# v1.net
KiCad netlist of a schematic drawn in EAGLE
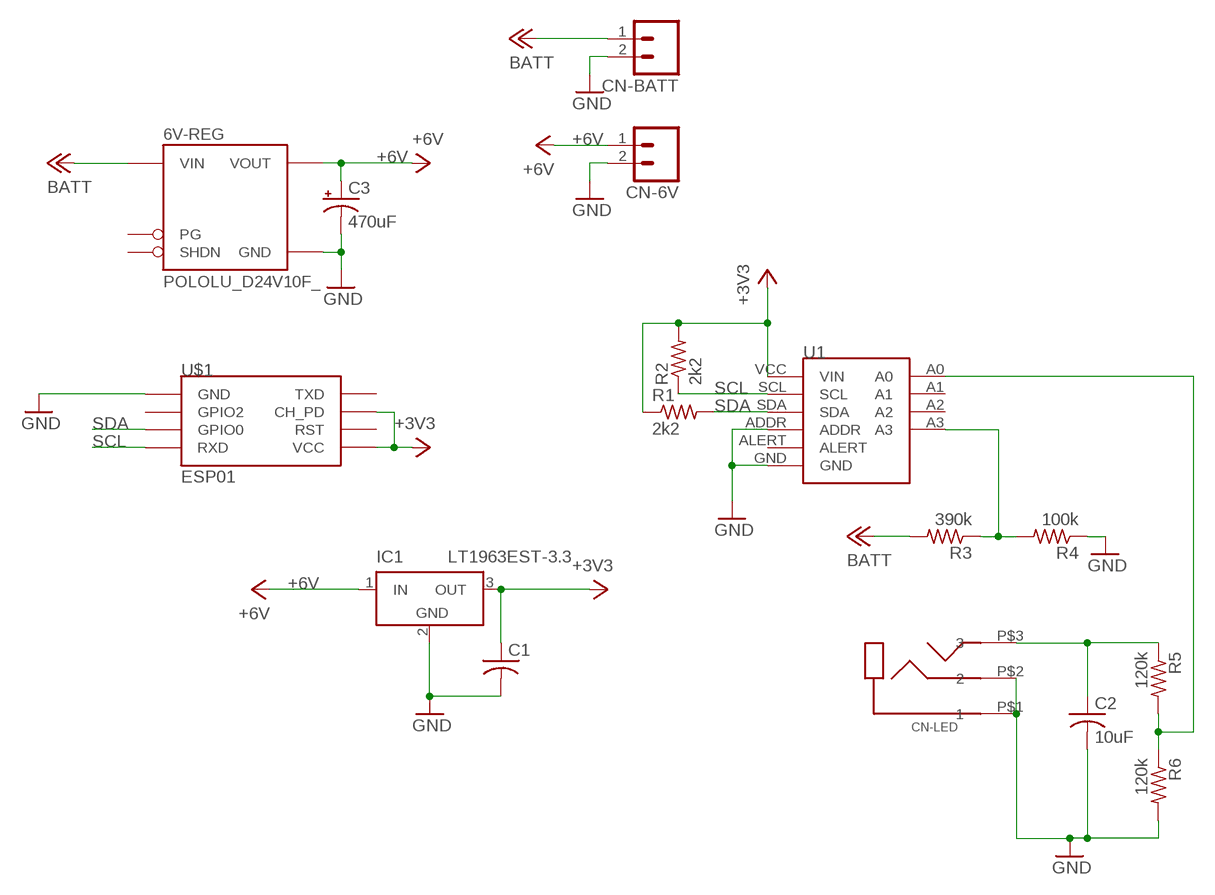
[diagram p0: schematic, sheet 1]

(export (version "E")
  (design (tool "Eeschema 10.0.6"))
  (components
    (comp (ref "6V-REG")
      (value "POLOLU_D24V10F_")
      (footprint "eagle-import:POLOLU_D24V10")
      (libsource (lib "eagle-import") (part "POLOLU_D24V10F_"))
    )
    (comp (ref "C1")
      (value "C-USC1210")
      (footprint "eagle-import:C1210")
      (libsource (lib "eagle-import") (part "C-USC1210"))
    )
    (comp (ref "C2")
      (value "10uF")
      (footprint "eagle-import:C0805K")
      (libsource (lib "eagle-import") (part "C-USC0805K"))
    )
    (comp (ref "C3")
      (value "470uF")
      (footprint "eagle-import:CPOL-RADIAL-2.5MM-6.5MM")
      (libsource (lib "eagle-import") (part "100UF-POLAR-RADIAL-2.5MM-25V-20%"))
    )
    (comp (ref "CN-6V")
      (value "M02")
      (footprint "eagle-import:02P")
      (libsource (lib "eagle-import") (part "M02"))
    )
    (comp (ref "CN-BATT")
      (value "M02")
      (footprint "eagle-import:02P")
      (libsource (lib "eagle-import") (part "M02"))
    )
    (comp (ref "CN-LED")
      (value "PJ-320B")
      (footprint "eagle-import:PJ-320B")
      (libsource (lib "eagle-import") (part "PJ-320B"))
    )
    (comp (ref "IC1")
      (value "LT1963EST-3.3")
      (footprint "eagle-import:SOT223")
      (libsource (lib "eagle-import") (part "LT1963EST-3.3"))
    )
    (comp (ref "R1")
      (value "2k2")
      (footprint "eagle-import:R0603")
      (libsource (lib "eagle-import") (part "R-US_R0603"))
    )
    (comp (ref "R2")
      (value "2k2")
      (footprint "eagle-import:R0603")
      (libsource (lib "eagle-import") (part "R-US_R0603"))
    )
    (comp (ref "R3")
      (value "390k")
      (footprint "eagle-import:R0603")
      (libsource (lib "eagle-import") (part "R-US_R0603"))
    )
    (comp (ref "R4")
      (value "100k")
      (footprint "eagle-import:R0603")
      (libsource (lib "eagle-import") (part "R-US_R0603"))
    )
    (comp (ref "R5")
      (value "120k")
      (footprint "eagle-import:R0603")
      (libsource (lib "eagle-import") (part "R-US_R0603"))
    )
    (comp (ref "R6")
      (value "120k")
      (footprint "eagle-import:R0603")
      (libsource (lib "eagle-import") (part "R-US_R0603"))
    )
    (comp (ref "U$1")
      (value "ESP01")
      (footprint "eagle-import:ESP01")
      (libsource (lib "eagle-import") (part "ESP01"))
    )
    (comp (ref "U1")
      (value "GY-ADS1115THM")
      (footprint "eagle-import:GY-ADS1115-THM")
      (libsource (lib "eagle-import") (part "GY-ADS1115THM"))
    )
  )
  (nets
    (net (code "1") (name "+3V3") (class "Default")
      (node (ref "C1") (pin "1") (pinfunction "1_1") (pintype "passive"))
      (node (ref "IC1") (pin "3") (pinfunction "OUT_3") (pintype "output"))
      (node (ref "R1") (pin "1") (pinfunction "1_1") (pintype "passive"))
      (node (ref "R2") (pin "2") (pinfunction "2_2") (pintype "passive"))
      (node (ref "U$1") (pin "CH_PD") (pinfunction "CH_PD_CH_PD") (pintype "bidirectional"))
      (node (ref "U$1") (pin "VCC") (pinfunction "VCC_VCC") (pintype "bidirectional"))
      (node (ref "U1") (pin "VCC") (pinfunction "VIN_VCC") (pintype "bidirectional"))
    )
    (net (code "2") (name "+6V") (class "Default")
      (node (ref "6V-REG") (pin "VOUT") (pinfunction "VOUT_VOUT") (pintype "output"))
      (node (ref "C3") (pin "1") (pinfunction "+_1") (pintype "passive"))
      (node (ref "CN-6V") (pin "1") (pinfunction "1_1") (pintype "passive"))
      (node (ref "IC1") (pin "1") (pinfunction "IN_1") (pintype "input"))
    )
    (net (code "3") (name "/SCL") (class "Default")
      (node (ref "R2") (pin "1") (pinfunction "1_1") (pintype "passive"))
      (node (ref "U$1") (pin "RX") (pinfunction "RXD_RX") (pintype "bidirectional"))
      (node (ref "U1") (pin "SCL") (pinfunction "SCL_SCL") (pintype "bidirectional"))
    )
    (net (code "4") (name "/SDA") (class "Default")
      (node (ref "R1") (pin "2") (pinfunction "2_2") (pintype "passive"))
      (node (ref "U$1") (pin "GPIO0") (pinfunction "GPIO0_GPIO0") (pintype "bidirectional"))
      (node (ref "U1") (pin "SDA") (pinfunction "SDA_SDA") (pintype "bidirectional"))
    )
    (net (code "5") (name "BATT") (class "Default")
      (node (ref "6V-REG") (pin "VIN") (pinfunction "VIN_VIN") (pintype "power_in"))
      (node (ref "CN-BATT") (pin "1") (pinfunction "1_1") (pintype "passive"))
      (node (ref "R3") (pin "2") (pinfunction "2_2") (pintype "passive"))
    )
    (net (code "6") (name "GND") (class "Default")
      (node (ref "6V-REG") (pin "GND") (pinfunction "GND_GND") (pintype "power_in"))
      (node (ref "C1") (pin "2") (pinfunction "2_2") (pintype "passive"))
      (node (ref "C2") (pin "2") (pinfunction "2_2") (pintype "passive"))
      (node (ref "C3") (pin "2") (pinfunction "-_2") (pintype "passive"))
      (node (ref "CN-6V") (pin "2") (pinfunction "2_2") (pintype "passive"))
      (node (ref "CN-BATT") (pin "2") (pinfunction "2_2") (pintype "passive"))
      (node (ref "CN-LED") (pin "P$1") (pinfunction "1_P$1") (pintype "bidirectional"))
      (node (ref "CN-LED") (pin "P$2") (pinfunction "2_P$2") (pintype "bidirectional"))
      (node (ref "IC1") (pin "2") (pinfunction "GND_2") (pintype "power_in"))
      (node (ref "R4") (pin "1") (pinfunction "1_1") (pintype "passive"))
      (node (ref "R6") (pin "2") (pinfunction "2_2") (pintype "passive"))
      (node (ref "U$1") (pin "GND") (pinfunction "GND_GND") (pintype "bidirectional"))
      (node (ref "U1") (pin "ADDR") (pinfunction "ADDR_ADDR") (pintype "bidirectional"))
      (node (ref "U1") (pin "GND") (pinfunction "GND_GND") (pintype "bidirectional"))
    )
    (net (code "7") (name "Net-(CN-LED-3)") (class "Default")
      (node (ref "C2") (pin "1") (pinfunction "1_1") (pintype "passive"))
      (node (ref "CN-LED") (pin "P$3") (pinfunction "3_P$3") (pintype "bidirectional"))
      (node (ref "R5") (pin "1") (pinfunction "1_1") (pintype "passive"))
    )
    (net (code "8") (name "Net-(R3-Pad1)") (class "Default")
      (node (ref "R3") (pin "1") (pinfunction "1_1") (pintype "passive"))
      (node (ref "R4") (pin "2") (pinfunction "2_2") (pintype "passive"))
      (node (ref "U1") (pin "A3") (pinfunction "A3_A3") (pintype "bidirectional"))
    )
    (net (code "9") (name "Net-(R5-Pad2)") (class "Default")
      (node (ref "R5") (pin "2") (pinfunction "2_2") (pintype "passive"))
      (node (ref "R6") (pin "1") (pinfunction "1_1") (pintype "passive"))
      (node (ref "U1") (pin "A0") (pinfunction "A0_A0") (pintype "bidirectional"))
    )
    (net (code "10") (name "unconnected-(6V-REG-PadPG)") (class "Default")
      (node (ref "6V-REG") (pin "PG") (pinfunction "PG_PG") (pintype "output"))
    )
    (net (code "11") (name "unconnected-(6V-REG-PadSHDN)") (class "Default")
      (node (ref "6V-REG") (pin "SHDN") (pinfunction "SHDN_SHDN") (pintype "input"))
    )
    (net (code "12") (name "unconnected-(U$1-PadGPIO2)") (class "Default")
      (node (ref "U$1") (pin "GPIO2") (pinfunction "GPIO2_GPIO2") (pintype "bidirectional"))
    )
    (net (code "13") (name "unconnected-(U$1-PadRST)") (class "Default")
      (node (ref "U$1") (pin "RST") (pinfunction "RST_RST") (pintype "bidirectional"))
    )
    (net (code "14") (name "unconnected-(U$1-TXD-PadTX)") (class "Default")
      (node (ref "U$1") (pin "TX") (pinfunction "TXD_TX") (pintype "bidirectional"))
    )
    (net (code "15") (name "unconnected-(U1-PadA1)") (class "Default")
      (node (ref "U1") (pin "A1") (pinfunction "A1_A1") (pintype "bidirectional"))
    )
    (net (code "16") (name "unconnected-(U1-PadA2)") (class "Default")
      (node (ref "U1") (pin "A2") (pinfunction "A2_A2") (pintype "bidirectional"))
    )
    (net (code "17") (name "unconnected-(U1-PadALERT)") (class "Default")
      (node (ref "U1") (pin "ALERT") (pinfunction "ALERT_ALERT") (pintype "bidirectional"))
    )
  )
)
